# teamNACHOrev2.net
KiCad netlist of a schematic drawn in EAGLE
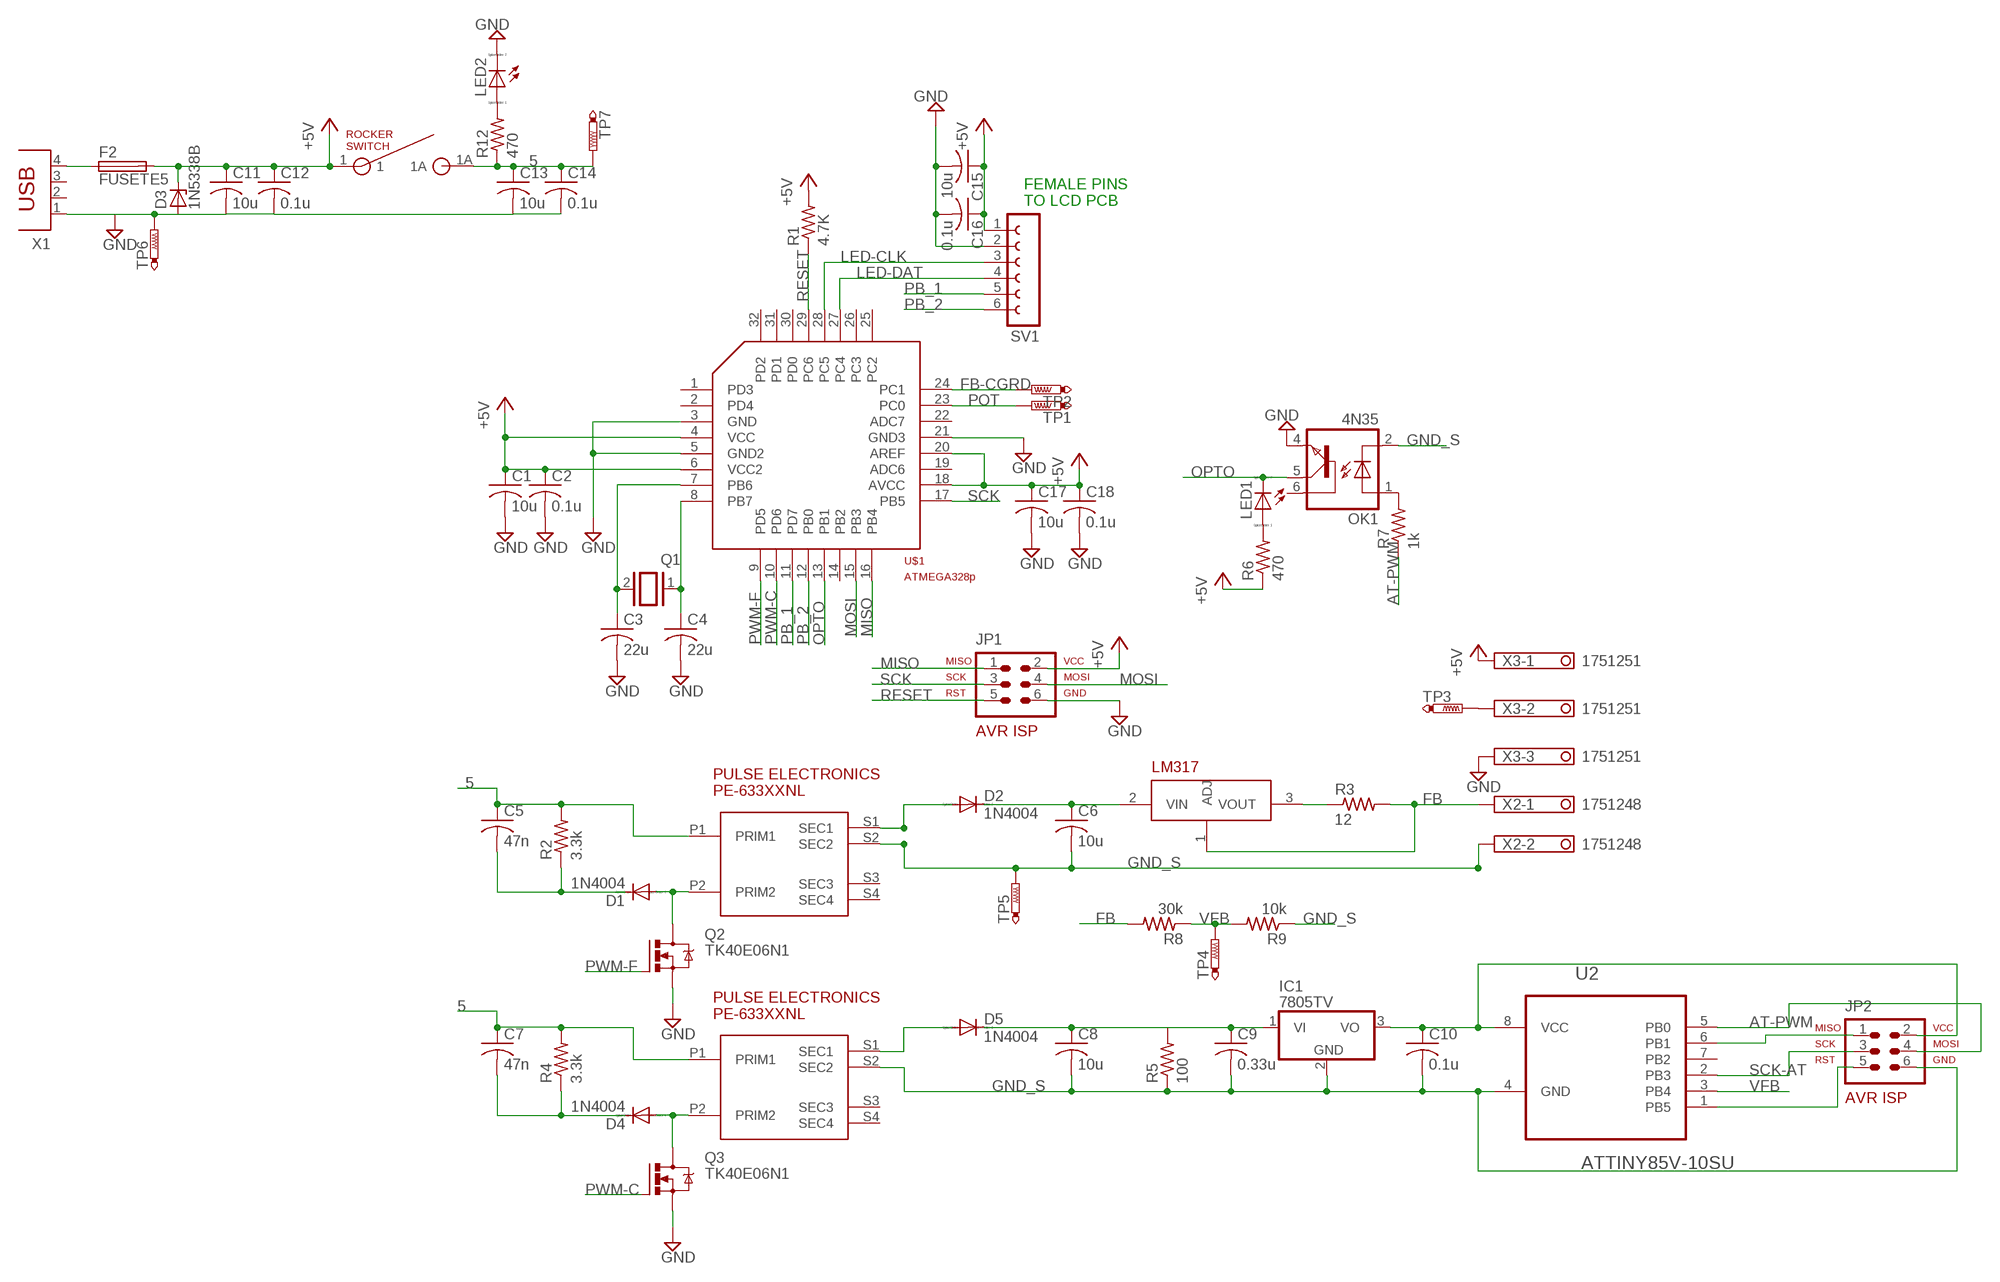
[diagram p0: schematic, sheet 1]

(export (version "E")
  (design (tool "Eeschema 10.0.6"))
  (components
    (comp (ref "C1")
      (value "10u")
      (footprint "eagle-import:C0805")
      (libsource (lib "eagle-import") (part "C-USC0805"))
    )
    (comp (ref "C2")
      (value "0.1u")
      (footprint "eagle-import:C0805")
      (libsource (lib "eagle-import") (part "C-USC0805"))
    )
    (comp (ref "C3")
      (value "22u")
      (footprint "eagle-import:C0805")
      (libsource (lib "eagle-import") (part "C-USC0805"))
    )
    (comp (ref "C4")
      (value "22u")
      (footprint "eagle-import:C0805")
      (libsource (lib "eagle-import") (part "C-USC0805"))
    )
    (comp (ref "C5")
      (value "47n")
      (footprint "eagle-import:C0805")
      (libsource (lib "eagle-import") (part "C-USC0805"))
    )
    (comp (ref "C6")
      (value "10u")
      (footprint "eagle-import:C0805")
      (libsource (lib "eagle-import") (part "C-USC0805"))
    )
    (comp (ref "C7")
      (value "47n")
      (footprint "eagle-import:C0805")
      (libsource (lib "eagle-import") (part "C-USC0805"))
    )
    (comp (ref "C8")
      (value "10u")
      (footprint "eagle-import:C0805")
      (libsource (lib "eagle-import") (part "C-USC0805"))
    )
    (comp (ref "C9")
      (value "0.33u")
      (footprint "eagle-import:C0805")
      (libsource (lib "eagle-import") (part "C-USC0805"))
    )
    (comp (ref "C10")
      (value "0.1u")
      (footprint "eagle-import:C0805")
      (libsource (lib "eagle-import") (part "C-USC0805"))
    )
    (comp (ref "C11")
      (value "10u")
      (footprint "eagle-import:C0805")
      (libsource (lib "eagle-import") (part "C-USC0805"))
    )
    (comp (ref "C12")
      (value "0.1u")
      (footprint "eagle-import:C0805")
      (libsource (lib "eagle-import") (part "C-USC0805"))
    )
    (comp (ref "C13")
      (value "10u")
      (footprint "eagle-import:C0805")
      (libsource (lib "eagle-import") (part "C-USC0805"))
    )
    (comp (ref "C14")
      (value "0.1u")
      (footprint "eagle-import:C0805")
      (libsource (lib "eagle-import") (part "C-USC0805"))
    )
    (comp (ref "C15")
      (value "10u")
      (footprint "eagle-import:C0805")
      (libsource (lib "eagle-import") (part "C-USC0805"))
    )
    (comp (ref "C16")
      (value "0.1u")
      (footprint "eagle-import:C0805")
      (libsource (lib "eagle-import") (part "C-USC0805"))
    )
    (comp (ref "C17")
      (value "10u")
      (footprint "eagle-import:C0805")
      (libsource (lib "eagle-import") (part "C-USC0805"))
    )
    (comp (ref "C18")
      (value "0.1u")
      (footprint "eagle-import:C0805")
      (libsource (lib "eagle-import") (part "C-USC0805"))
    )
    (comp (ref "D1")
      (value "1N4004")
      (footprint "eagle-import:DO41-10")
      (libsource (lib "eagle-import") (part "1N4004"))
    )
    (comp (ref "D2")
      (value "1N4004")
      (footprint "eagle-import:DO41-10")
      (libsource (lib "eagle-import") (part "1N4004"))
    )
    (comp (ref "D3")
      (value "1N5338B")
      (footprint "eagle-import:C1702-15")
      (libsource (lib "eagle-import") (part "1N5333"))
    )
    (comp (ref "D4")
      (value "1N4004")
      (footprint "eagle-import:DO41-10")
      (libsource (lib "eagle-import") (part "1N4004"))
    )
    (comp (ref "D5")
      (value "1N4004")
      (footprint "eagle-import:DO41-10")
      (libsource (lib "eagle-import") (part "1N4004"))
    )
    (comp (ref "F2")
      (value "FUSETE5")
      (footprint "eagle-import:TE5")
      (libsource (lib "eagle-import") (part "FUSETE5"))
    )
    (comp (ref "IC1")
      (value "7805TV")
      (footprint "eagle-import:TO220V")
      (libsource (lib "eagle-import") (part "78TV05"))
    )
    (comp (ref "JP1")
      (value "AVR-ISP-6VERT")
      (footprint "eagle-import:AVR-ISP-6")
      (libsource (lib "eagle-import") (part "AVR-ISP-6VERT"))
    )
    (comp (ref "JP2")
      (value "AVR-ISP-6VERT")
      (footprint "eagle-import:AVR-ISP-6")
      (libsource (lib "eagle-import") (part "AVR-ISP-6VERT"))
    )
    (comp (ref "LED1")
      (value "LED_ELD260")
      (footprint "eagle-import:LED_LD260")
      (libsource (lib "eagle-import") (part "LED_ELD260"))
    )
    (comp (ref "LED2")
      (value "LED_ELD260")
      (footprint "eagle-import:LED_LD260")
      (libsource (lib "eagle-import") (part "LED_ELD260"))
    )
    (comp (ref "OK1")
      (value "4N35")
      (footprint "eagle-import:DIL06")
      (fields (field (name "MF") "FAIRCHILD SEMICONDUCTOR"))
      (libsource (lib "eagle-import") (part "4N35"))
    )
    (comp (ref "Q1")
      (value "XTAL/S")
      (footprint "eagle-import:QS")
      (libsource (lib "eagle-import") (part "XTAL/S"))
    )
    (comp (ref "Q2")
      (value "TK40E06N1")
      (footprint "eagle-import:TO220BV")
      (libsource (lib "eagle-import") (part "IRF520"))
    )
    (comp (ref "Q3")
      (value "TK40E06N1")
      (footprint "eagle-import:TO220BV")
      (libsource (lib "eagle-import") (part "IRF520"))
    )
    (comp (ref "R1")
      (value "4.7K")
      (footprint "eagle-import:R0805")
      (libsource (lib "eagle-import") (part "R-US_R0805"))
    )
    (comp (ref "R2")
      (value "3.3k")
      (footprint "eagle-import:R0805")
      (libsource (lib "eagle-import") (part "resistor_R-US_R0805"))
    )
    (comp (ref "R3")
      (value "12")
      (footprint "eagle-import:M0805")
      (libsource (lib "eagle-import") (part "R-US_M0805"))
    )
    (comp (ref "R4")
      (value "3.3k")
      (footprint "eagle-import:R0805")
      (libsource (lib "eagle-import") (part "resistor_R-US_R0805"))
    )
    (comp (ref "R5")
      (value "100")
      (footprint "eagle-import:R0805")
      (libsource (lib "eagle-import") (part "resistor_R-US_R0805"))
    )
    (comp (ref "R6")
      (value "470")
      (footprint "eagle-import:M0805")
      (libsource (lib "eagle-import") (part "R-US_M0805"))
    )
    (comp (ref "R7")
      (value "1k")
      (footprint "eagle-import:M0805")
      (libsource (lib "eagle-import") (part "R-US_M0805"))
    )
    (comp (ref "R8")
      (value "30k")
      (footprint "eagle-import:R0805")
      (libsource (lib "eagle-import") (part "resistor_R-US_R0805"))
    )
    (comp (ref "R9")
      (value "10k")
      (footprint "eagle-import:R0805")
      (libsource (lib "eagle-import") (part "resistor_R-US_R0805"))
    )
    (comp (ref "R12")
      (value "470")
      (footprint "eagle-import:M0805")
      (libsource (lib "eagle-import") (part "R-US_M0805"))
    )
    (comp (ref "SV1")
      (value "FE06-1")
      (footprint "eagle-import:FE06")
      (libsource (lib "eagle-import") (part "FE06-1"))
    )
    (comp (ref "TP1")
      (value "PTR1PAD1-20")
      (footprint "eagle-import:P1-20")
      (libsource (lib "eagle-import") (part "PTR1PAD1-20"))
    )
    (comp (ref "TP2")
      (value "PTR1PAD1-20")
      (footprint "eagle-import:P1-20")
      (libsource (lib "eagle-import") (part "PTR1PAD1-20"))
    )
    (comp (ref "TP3")
      (value "PTR1PAD1-20")
      (footprint "eagle-import:P1-20")
      (libsource (lib "eagle-import") (part "PTR1PAD1-20"))
    )
    (comp (ref "TP4")
      (value "PTR1PAD1-20")
      (footprint "eagle-import:P1-20")
      (libsource (lib "eagle-import") (part "PTR1PAD1-20"))
    )
    (comp (ref "TP5")
      (value "PTR1PAD1-20")
      (footprint "eagle-import:P1-20")
      (libsource (lib "eagle-import") (part "PTR1PAD1-20"))
    )
    (comp (ref "TP6")
      (value "PTR1PAD1-20")
      (footprint "eagle-import:P1-20")
      (libsource (lib "eagle-import") (part "PTR1PAD1-20"))
    )
    (comp (ref "TP7")
      (value "PTR1PAD1-20")
      (footprint "eagle-import:P1-20")
      (libsource (lib "eagle-import") (part "PTR1PAD1-20"))
    )
    (comp (ref "U$1")
      (value "ATMEGA328P")
      (footprint "eagle-import:TQFP32")
      (libsource (lib "eagle-import") (part "ATMEGA328P"))
    )
    (comp (ref "U$2")
      (value "PE-63388NL")
      (footprint "eagle-import:PE-633XXNL")
      (libsource (lib "eagle-import") (part "PE-63388NL"))
    )
    (comp (ref "U$3")
      (value "LM317")
      (footprint "eagle-import:TO220V")
      (libsource (lib "eagle-import") (part "LM317"))
    )
    (comp (ref "U$4")
      (value "COM-08837")
      (footprint "eagle-import:ROCKERSWITCH")
      (libsource (lib "eagle-import") (part "COM-08837"))
    )
    (comp (ref "U$5")
      (value "PE-63388NL")
      (footprint "eagle-import:PE-633XXNL")
      (libsource (lib "eagle-import") (part "PE-63388NL"))
    )
    (comp (ref "U2")
      (value "ATTINY85V-10SU")
      (footprint "eagle-import:SOIC127P798X216-8N")
      (libsource (lib "eagle-import") (part "ATTINY85V-10SU"))
    )
    (comp (ref "X1")
      (value "PN87520")
      (footprint "eagle-import:PN87520")
      (libsource (lib "eagle-import") (part "PN87520"))
    )
    (comp (ref "X2")
      (value "1751248")
      (footprint "eagle-import:1751248")
      (libsource (lib "eagle-import") (part "1751248"))
    )
    (comp (ref "X3")
      (value "1751251")
      (footprint "eagle-import:1751251")
      (libsource (lib "eagle-import") (part "1751251"))
    )
  )
  (nets
    (net (code "1") (name "+5V") (class "Default")
      (node (ref "C1") (pin "1") (pinfunction "1_1") (pintype "passive"))
      (node (ref "C11") (pin "1") (pinfunction "1_1") (pintype "passive"))
      (node (ref "C12") (pin "1") (pinfunction "1_1") (pintype "passive"))
      (node (ref "C15") (pin "1") (pinfunction "1_1") (pintype "passive"))
      (node (ref "C16") (pin "1") (pinfunction "1_1") (pintype "passive"))
      (node (ref "C17") (pin "1") (pinfunction "1_1") (pintype "passive"))
      (node (ref "C18") (pin "1") (pinfunction "1_1") (pintype "passive"))
      (node (ref "C2") (pin "1") (pinfunction "1_1") (pintype "passive"))
      (node (ref "D3") (pin "C") (pinfunction "C_C") (pintype "passive"))
      (node (ref "F2") (pin "2") (pinfunction "2_2") (pintype "passive"))
      (node (ref "JP1") (pin "2") (pinfunction "2_2") (pintype "passive"))
      (node (ref "R1") (pin "2") (pinfunction "2_2") (pintype "passive"))
      (node (ref "R6") (pin "1") (pinfunction "1_1") (pintype "passive"))
      (node (ref "SV1") (pin "1") (pinfunction "1_1") (pintype "passive"))
      (node (ref "U$1") (pin "18") (pinfunction "AVCC_18") (pintype "bidirectional"))
      (node (ref "U$1") (pin "20") (pinfunction "AREF_20") (pintype "bidirectional"))
      (node (ref "U$1") (pin "4") (pinfunction "VCC_4") (pintype "bidirectional"))
      (node (ref "U$1") (pin "6") (pinfunction "VCC2_6") (pintype "bidirectional"))
      (node (ref "U$4") (pin "1") (pinfunction "1_1") (pintype "bidirectional"))
      (node (ref "X3") (pin "1") (pinfunction "K_1") (pintype "passive"))
    )
    (net (code "2") (name "/5") (class "Default")
      (node (ref "C13") (pin "1") (pinfunction "1_1") (pintype "passive"))
      (node (ref "C14") (pin "1") (pinfunction "1_1") (pintype "passive"))
      (node (ref "C5") (pin "1") (pinfunction "1_1") (pintype "passive"))
      (node (ref "C7") (pin "1") (pinfunction "1_1") (pintype "passive"))
      (node (ref "R12") (pin "1") (pinfunction "1_1") (pintype "passive"))
      (node (ref "R2") (pin "2") (pinfunction "2_2") (pintype "passive"))
      (node (ref "R4") (pin "2") (pinfunction "2_2") (pintype "passive"))
      (node (ref "TP7") (pin "TP") (pinfunction "TP_TP") (pintype "input"))
      (node (ref "U$2") (pin "P1") (pinfunction "PRIM1_P1") (pintype "bidirectional"))
      (node (ref "U$4") (pin "1A") (pinfunction "1A_1A") (pintype "bidirectional"))
      (node (ref "U$5") (pin "P1") (pinfunction "PRIM1_P1") (pintype "bidirectional"))
    )
    (net (code "3") (name "/AT-PWM") (class "Default")
      (node (ref "JP2") (pin "4") (pinfunction "4_4") (pintype "passive"))
      (node (ref "R7") (pin "1") (pinfunction "1_1") (pintype "passive"))
      (node (ref "U2") (pin "5") (pinfunction "PB0_5") (pintype "bidirectional"))
    )
    (net (code "4") (name "/FB") (class "Default")
      (node (ref "R3") (pin "2") (pinfunction "2_2") (pintype "passive"))
      (node (ref "R8") (pin "2") (pinfunction "2_2") (pintype "passive"))
      (node (ref "U$3") (pin "1") (pinfunction "ADJ_1") (pintype "bidirectional"))
      (node (ref "X2") (pin "1") (pinfunction "K_1") (pintype "passive"))
    )
    (net (code "5") (name "/FB-CGRD") (class "Default")
      (node (ref "TP2") (pin "TP") (pinfunction "TP_TP") (pintype "input"))
      (node (ref "U$1") (pin "24") (pinfunction "PC1_24") (pintype "bidirectional"))
    )
    (net (code "6") (name "/GND_S") (class "Default")
      (node (ref "C10") (pin "2") (pinfunction "2_2") (pintype "passive"))
      (node (ref "C6") (pin "2") (pinfunction "2_2") (pintype "passive"))
      (node (ref "C8") (pin "2") (pinfunction "2_2") (pintype "passive"))
      (node (ref "C9") (pin "2") (pinfunction "2_2") (pintype "passive"))
      (node (ref "IC1") (pin "2") (pinfunction "GND_2") (pintype "passive"))
      (node (ref "JP2") (pin "6") (pinfunction "6_6") (pintype "passive"))
      (node (ref "OK1") (pin "2") (pinfunction "C_2") (pintype "passive"))
      (node (ref "R5") (pin "1") (pinfunction "1_1") (pintype "passive"))
      (node (ref "R9") (pin "1") (pinfunction "1_1") (pintype "passive"))
      (node (ref "TP5") (pin "TP") (pinfunction "TP_TP") (pintype "input"))
      (node (ref "U$2") (pin "S2") (pinfunction "SEC2_S2") (pintype "bidirectional"))
      (node (ref "U$5") (pin "S2") (pinfunction "SEC2_S2") (pintype "bidirectional"))
      (node (ref "U2") (pin "4") (pinfunction "GND_4") (pintype "passive"))
      (node (ref "X2") (pin "2") (pinfunction "K_2") (pintype "passive"))
    )
    (net (code "7") (name "/LED-CLK") (class "Default")
      (node (ref "SV1") (pin "3") (pinfunction "3_3") (pintype "passive"))
      (node (ref "U$1") (pin "28") (pinfunction "PC5_28") (pintype "bidirectional"))
    )
    (net (code "8") (name "/LED-DAT") (class "Default")
      (node (ref "SV1") (pin "4") (pinfunction "4_4") (pintype "passive"))
      (node (ref "U$1") (pin "27") (pinfunction "PC4_27") (pintype "bidirectional"))
    )
    (net (code "9") (name "/MISO") (class "Default")
      (node (ref "JP1") (pin "1") (pinfunction "1_1") (pintype "passive"))
      (node (ref "U$1") (pin "16") (pinfunction "PB4_16") (pintype "bidirectional"))
    )
    (net (code "10") (name "/MOSI") (class "Default")
      (node (ref "JP1") (pin "4") (pinfunction "4_4") (pintype "passive"))
      (node (ref "U$1") (pin "15") (pinfunction "PB3_15") (pintype "bidirectional"))
    )
    (net (code "11") (name "/OPTO") (class "Default")
      (node (ref "LED1") (pin "K") (pinfunction "C_K") (pintype "passive"))
      (node (ref "OK1") (pin "5") (pinfunction "COL_5") (pintype "passive"))
      (node (ref "U$1") (pin "13") (pinfunction "PB1_13") (pintype "bidirectional"))
    )
    (net (code "12") (name "/PB_1") (class "Default")
      (node (ref "SV1") (pin "5") (pinfunction "5_5") (pintype "passive"))
      (node (ref "U$1") (pin "11") (pinfunction "PD7_11") (pintype "bidirectional"))
    )
    (net (code "13") (name "/PB_2") (class "Default")
      (node (ref "SV1") (pin "6") (pinfunction "6_6") (pintype "passive"))
      (node (ref "U$1") (pin "12") (pinfunction "PB0_12") (pintype "bidirectional"))
    )
    (net (code "14") (name "/POT") (class "Default")
      (node (ref "TP1") (pin "TP") (pinfunction "TP_TP") (pintype "input"))
      (node (ref "U$1") (pin "23") (pinfunction "PC0_23") (pintype "bidirectional"))
    )
    (net (code "15") (name "/PWM-C") (class "Default")
      (node (ref "Q3") (pin "G") (pinfunction "G_G") (pintype "passive"))
      (node (ref "U$1") (pin "10") (pinfunction "PD6_10") (pintype "bidirectional"))
    )
    (net (code "16") (name "/PWM-F") (class "Default")
      (node (ref "Q2") (pin "G") (pinfunction "G_G") (pintype "passive"))
      (node (ref "U$1") (pin "9") (pinfunction "PD5_9") (pintype "bidirectional"))
    )
    (net (code "17") (name "/RESET") (class "Default")
      (node (ref "JP1") (pin "5") (pinfunction "5_5") (pintype "passive"))
      (node (ref "R1") (pin "1") (pinfunction "1_1") (pintype "passive"))
      (node (ref "U$1") (pin "29") (pinfunction "PC6_29") (pintype "bidirectional"))
    )
    (net (code "18") (name "/SCK") (class "Default")
      (node (ref "JP1") (pin "3") (pinfunction "3_3") (pintype "passive"))
      (node (ref "U$1") (pin "17") (pinfunction "PB5_17") (pintype "bidirectional"))
    )
    (net (code "19") (name "/SCK-AT") (class "Default")
      (node (ref "JP2") (pin "3") (pinfunction "3_3") (pintype "passive"))
      (node (ref "U2") (pin "2") (pinfunction "PB3_2") (pintype "bidirectional"))
    )
    (net (code "20") (name "/VFB") (class "Default")
      (node (ref "R8") (pin "1") (pinfunction "1_1") (pintype "passive"))
      (node (ref "R9") (pin "2") (pinfunction "2_2") (pintype "passive"))
      (node (ref "TP4") (pin "TP") (pinfunction "TP_TP") (pintype "input"))
      (node (ref "U2") (pin "3") (pinfunction "PB4_3") (pintype "bidirectional"))
    )
    (net (code "21") (name "GND") (class "Default")
      (node (ref "C1") (pin "2") (pinfunction "2_2") (pintype "passive"))
      (node (ref "C11") (pin "2") (pinfunction "2_2") (pintype "passive"))
      (node (ref "C12") (pin "2") (pinfunction "2_2") (pintype "passive"))
      (node (ref "C13") (pin "2") (pinfunction "2_2") (pintype "passive"))
      (node (ref "C14") (pin "2") (pinfunction "2_2") (pintype "passive"))
      (node (ref "C15") (pin "2") (pinfunction "2_2") (pintype "passive"))
      (node (ref "C16") (pin "2") (pinfunction "2_2") (pintype "passive"))
      (node (ref "C17") (pin "2") (pinfunction "2_2") (pintype "passive"))
      (node (ref "C18") (pin "2") (pinfunction "2_2") (pintype "passive"))
      (node (ref "C2") (pin "2") (pinfunction "2_2") (pintype "passive"))
      (node (ref "C3") (pin "2") (pinfunction "2_2") (pintype "passive"))
      (node (ref "C4") (pin "2") (pinfunction "2_2") (pintype "passive"))
      (node (ref "D3") (pin "A") (pinfunction "A_A") (pintype "passive"))
      (node (ref "JP1") (pin "6") (pinfunction "6_6") (pintype "passive"))
      (node (ref "LED2") (pin "K") (pinfunction "C_K") (pintype "passive"))
      (node (ref "OK1") (pin "4") (pinfunction "EMI_4") (pintype "passive"))
      (node (ref "Q2") (pin "S") (pinfunction "S_S") (pintype "passive"))
      (node (ref "Q3") (pin "S") (pinfunction "S_S") (pintype "passive"))
      (node (ref "SV1") (pin "2") (pinfunction "2_2") (pintype "passive"))
      (node (ref "TP6") (pin "TP") (pinfunction "TP_TP") (pintype "input"))
      (node (ref "U$1") (pin "21") (pinfunction "GND3_21") (pintype "bidirectional"))
      (node (ref "U$1") (pin "3") (pinfunction "GND_3") (pintype "bidirectional"))
      (node (ref "U$1") (pin "5") (pinfunction "GND2_5") (pintype "bidirectional"))
      (node (ref "X1") (pin "1") (pinfunction "1_1") (pintype "passive"))
      (node (ref "X3") (pin "3") (pinfunction "K_3") (pintype "passive"))
    )
    (net (code "22") (name "Net-(C5-Pad2)") (class "Default")
      (node (ref "C5") (pin "2") (pinfunction "2_2") (pintype "passive"))
      (node (ref "D1") (pin "C") (pinfunction "C_C") (pintype "passive"))
      (node (ref "R2") (pin "1") (pinfunction "1_1") (pintype "passive"))
    )
    (net (code "23") (name "Net-(C7-Pad2)") (class "Default")
      (node (ref "C7") (pin "2") (pinfunction "2_2") (pintype "passive"))
      (node (ref "D4") (pin "C") (pinfunction "C_C") (pintype "passive"))
      (node (ref "R4") (pin "1") (pinfunction "1_1") (pintype "passive"))
    )
    (net (code "24") (name "Net-(F2-Pad1)") (class "Default")
      (node (ref "F2") (pin "1") (pinfunction "1_1") (pintype "passive"))
      (node (ref "X1") (pin "4") (pinfunction "4_4") (pintype "passive"))
    )
    (net (code "25") (name "Net-(IC1-VI)") (class "Default")
      (node (ref "C8") (pin "1") (pinfunction "1_1") (pintype "passive"))
      (node (ref "C9") (pin "1") (pinfunction "1_1") (pintype "passive"))
      (node (ref "D5") (pin "C") (pinfunction "C_C") (pintype "passive"))
      (node (ref "IC1") (pin "1") (pinfunction "VI_1") (pintype "input"))
      (node (ref "R5") (pin "2") (pinfunction "2_2") (pintype "passive"))
    )
    (net (code "26") (name "Net-(IC1-VO)") (class "Default")
      (node (ref "C10") (pin "1") (pinfunction "1_1") (pintype "passive"))
      (node (ref "IC1") (pin "3") (pinfunction "VO_3") (pintype "passive"))
      (node (ref "JP2") (pin "2") (pinfunction "2_2") (pintype "passive"))
      (node (ref "U2") (pin "8") (pinfunction "VCC_8") (pintype "power_in"))
    )
    (net (code "27") (name "Net-(LED1-PadA)") (class "Default")
      (node (ref "LED1") (pin "A") (pinfunction "A_A") (pintype "passive"))
      (node (ref "R6") (pin "2") (pinfunction "2_2") (pintype "passive"))
    )
    (net (code "28") (name "Net-(LED2-PadA)") (class "Default")
      (node (ref "LED2") (pin "A") (pinfunction "A_A") (pintype "passive"))
      (node (ref "R12") (pin "2") (pinfunction "2_2") (pintype "passive"))
    )
    (net (code "29") (name "Net-(OK1-A)") (class "Default")
      (node (ref "OK1") (pin "1") (pinfunction "A_1") (pintype "passive"))
      (node (ref "R7") (pin "2") (pinfunction "2_2") (pintype "passive"))
    )
    (net (code "30") (name "Net-(U$1-PB6)") (class "Default")
      (node (ref "C3") (pin "1") (pinfunction "1_1") (pintype "passive"))
      (node (ref "Q1") (pin "2") (pinfunction "2_2") (pintype "passive"))
      (node (ref "U$1") (pin "7") (pinfunction "PB6_7") (pintype "bidirectional"))
    )
    (net (code "31") (name "Net-(U$1-PB7)") (class "Default")
      (node (ref "C4") (pin "1") (pinfunction "1_1") (pintype "passive"))
      (node (ref "Q1") (pin "1") (pinfunction "1_1") (pintype "passive"))
      (node (ref "U$1") (pin "8") (pinfunction "PB7_8") (pintype "bidirectional"))
    )
    (net (code "32") (name "Net-(U$2-PRIM2)") (class "Default")
      (node (ref "D1") (pin "A") (pinfunction "A_A") (pintype "passive"))
      (node (ref "Q2") (pin "D") (pinfunction "D_D") (pintype "passive"))
      (node (ref "U$2") (pin "P2") (pinfunction "PRIM2_P2") (pintype "bidirectional"))
    )
    (net (code "33") (name "Net-(U$2-SEC1)") (class "Default")
      (node (ref "D2") (pin "A") (pinfunction "A_A") (pintype "passive"))
      (node (ref "U$2") (pin "S1") (pinfunction "SEC1_S1") (pintype "bidirectional"))
    )
    (net (code "34") (name "Net-(U$3-VIN)") (class "Default")
      (node (ref "C6") (pin "1") (pinfunction "1_1") (pintype "passive"))
      (node (ref "D2") (pin "C") (pinfunction "C_C") (pintype "passive"))
      (node (ref "U$3") (pin "2") (pinfunction "VIN_2") (pintype "bidirectional"))
    )
    (net (code "35") (name "Net-(U$3-VOUT)") (class "Default")
      (node (ref "R3") (pin "1") (pinfunction "1_1") (pintype "passive"))
      (node (ref "U$3") (pin "3") (pinfunction "VOUT_3") (pintype "bidirectional"))
    )
    (net (code "36") (name "Net-(U$5-PRIM2)") (class "Default")
      (node (ref "D4") (pin "A") (pinfunction "A_A") (pintype "passive"))
      (node (ref "Q3") (pin "D") (pinfunction "D_D") (pintype "passive"))
      (node (ref "U$5") (pin "P2") (pinfunction "PRIM2_P2") (pintype "bidirectional"))
    )
    (net (code "37") (name "Net-(U$5-SEC1)") (class "Default")
      (node (ref "D5") (pin "A") (pinfunction "A_A") (pintype "passive"))
      (node (ref "U$5") (pin "S1") (pinfunction "SEC1_S1") (pintype "bidirectional"))
    )
    (net (code "38") (name "Net-(U2-PB1)") (class "Default")
      (node (ref "JP2") (pin "1") (pinfunction "1_1") (pintype "passive"))
      (node (ref "U2") (pin "6") (pinfunction "PB1_6") (pintype "bidirectional"))
    )
    (net (code "39") (name "Net-(U2-PB5)") (class "Default")
      (node (ref "JP2") (pin "5") (pinfunction "5_5") (pintype "passive"))
      (node (ref "U2") (pin "1") (pinfunction "PB5_1") (pintype "bidirectional"))
    )
    (net (code "40") (name "Net-(X3B-K)") (class "Default")
      (node (ref "TP3") (pin "TP") (pinfunction "TP_TP") (pintype "input"))
      (node (ref "X3") (pin "2") (pinfunction "K_2") (pintype "passive"))
    )
    (net (code "41") (name "unconnected-(OK1-BAS-Pad6)") (class "Default")
      (node (ref "OK1") (pin "6") (pinfunction "BAS_6") (pintype "passive"))
    )
    (net (code "42") (name "unconnected-(U$1-ADC6-Pad19)") (class "Default")
      (node (ref "U$1") (pin "19") (pinfunction "ADC6_19") (pintype "bidirectional"))
    )
    (net (code "43") (name "unconnected-(U$1-ADC7-Pad22)") (class "Default")
      (node (ref "U$1") (pin "22") (pinfunction "ADC7_22") (pintype "bidirectional"))
    )
    (net (code "44") (name "unconnected-(U$1-PB2-Pad14)") (class "Default")
      (node (ref "U$1") (pin "14") (pinfunction "PB2_14") (pintype "bidirectional"))
    )
    (net (code "45") (name "unconnected-(U$1-PC2-Pad25)") (class "Default")
      (node (ref "U$1") (pin "25") (pinfunction "PC2_25") (pintype "bidirectional"))
    )
    (net (code "46") (name "unconnected-(U$1-PC3-Pad26)") (class "Default")
      (node (ref "U$1") (pin "26") (pinfunction "PC3_26") (pintype "bidirectional"))
    )
    (net (code "47") (name "unconnected-(U$1-PD0-Pad30)") (class "Default")
      (node (ref "U$1") (pin "30") (pinfunction "PD0_30") (pintype "bidirectional"))
    )
    (net (code "48") (name "unconnected-(U$1-PD1-Pad31)") (class "Default")
      (node (ref "U$1") (pin "31") (pinfunction "PD1_31") (pintype "bidirectional"))
    )
    (net (code "49") (name "unconnected-(U$1-PD2-Pad32)") (class "Default")
      (node (ref "U$1") (pin "32") (pinfunction "PD2_32") (pintype "bidirectional"))
    )
    (net (code "50") (name "unconnected-(U$1-PD3-Pad1)") (class "Default")
      (node (ref "U$1") (pin "1") (pinfunction "PD3_1") (pintype "bidirectional"))
    )
    (net (code "51") (name "unconnected-(U$1-PD4-Pad2)") (class "Default")
      (node (ref "U$1") (pin "2") (pinfunction "PD4_2") (pintype "bidirectional"))
    )
    (net (code "52") (name "unconnected-(U$2-SEC3-PadS3)") (class "Default")
      (node (ref "U$2") (pin "S3") (pinfunction "SEC3_S3") (pintype "bidirectional"))
    )
    (net (code "53") (name "unconnected-(U$2-SEC4-PadS4)") (class "Default")
      (node (ref "U$2") (pin "S4") (pinfunction "SEC4_S4") (pintype "bidirectional"))
    )
    (net (code "54") (name "unconnected-(U$5-SEC3-PadS3)") (class "Default")
      (node (ref "U$5") (pin "S3") (pinfunction "SEC3_S3") (pintype "bidirectional"))
    )
    (net (code "55") (name "unconnected-(U$5-SEC4-PadS4)") (class "Default")
      (node (ref "U$5") (pin "S4") (pinfunction "SEC4_S4") (pintype "bidirectional"))
    )
    (net (code "56") (name "unconnected-(U2-PB2-Pad7)") (class "Default")
      (node (ref "U2") (pin "7") (pinfunction "PB2_7") (pintype "bidirectional"))
    )
    (net (code "57") (name "unconnected-(X1-Pad2)") (class "Default")
      (node (ref "X1") (pin "2") (pinfunction "2_2") (pintype "passive"))
    )
    (net (code "58") (name "unconnected-(X1-Pad3)") (class "Default")
      (node (ref "X1") (pin "3") (pinfunction "3_3") (pintype "passive"))
    )
  )
)
